# Bathroom_Board.net
KiCad netlist of a schematic drawn in EAGLE
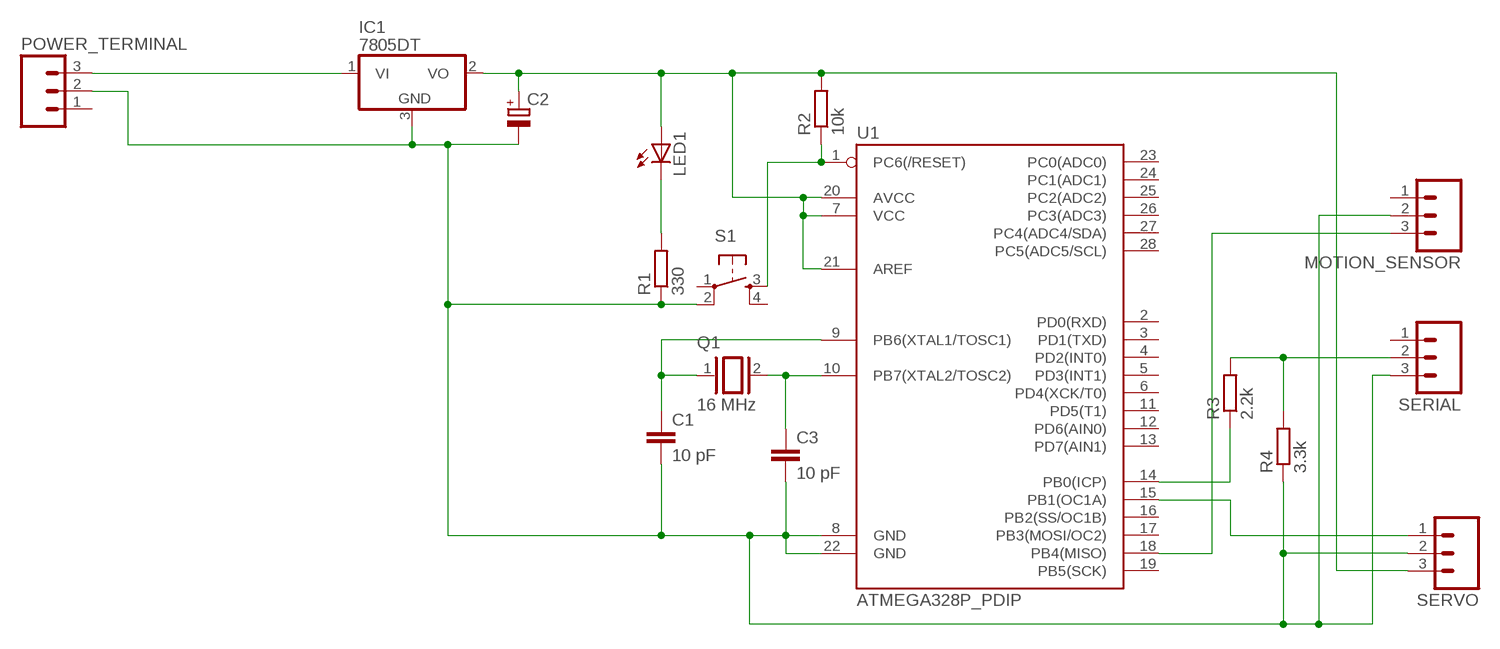
[diagram p0: schematic, sheet 1]

(export (version "E")
  (design (tool "Eeschema 10.0.6"))
  (components
    (comp (ref "C1")
      (value "10 pF")
      (footprint "eagle-import:C025-050X050")
      (libsource (lib "eagle-import") (part "C-EU025-050X050"))
    )
    (comp (ref "C2")
      (value "CPOL-EU153CLV-0505")
      (footprint "eagle-import:153CLV-0505")
      (libsource (lib "eagle-import") (part "CPOL-EU153CLV-0505"))
    )
    (comp (ref "C3")
      (value "10 pF")
      (footprint "eagle-import:C025-050X050")
      (libsource (lib "eagle-import") (part "C-EU025-050X050"))
    )
    (comp (ref "IC1")
      (value "7805DT")
      (footprint "eagle-import:TO252")
      (libsource (lib "eagle-import") (part "78DT05"))
    )
    (comp (ref "LED1")
      (value "LED5MM")
      (footprint "eagle-import:LED5MM")
      (libsource (lib "eagle-import") (part "LED5MM"))
    )
    (comp (ref "MOTION_SENSOR")
      (value "M03-SCREW-5MM")
      (footprint "eagle-import:SCREWTERMINAL-5MM-3")
      (libsource (lib "eagle-import") (part "M03-SCREW-5MM"))
    )
    (comp (ref "POWER_TERMINAL")
      (value "M03-SCREW-5MM")
      (footprint "eagle-import:SCREWTERMINAL-5MM-3")
      (libsource (lib "eagle-import") (part "M03-SCREW-5MM"))
    )
    (comp (ref "Q1")
      (value "16 MHz")
      (footprint "eagle-import:QS")
      (libsource (lib "eagle-import") (part "XTAL/S"))
    )
    (comp (ref "R1")
      (value "330")
      (footprint "eagle-import:0411_12")
      (libsource (lib "eagle-import") (part "R-EU_0411/12"))
    )
    (comp (ref "R2")
      (value "10k")
      (footprint "eagle-import:0411_12")
      (libsource (lib "eagle-import") (part "R-EU_0411/12"))
    )
    (comp (ref "R3")
      (value "2.2k")
      (footprint "eagle-import:0411_12")
      (libsource (lib "eagle-import") (part "R-EU_0411/12"))
    )
    (comp (ref "R4")
      (value "3.3k")
      (footprint "eagle-import:0411_12")
      (libsource (lib "eagle-import") (part "R-EU_0411/12"))
    )
    (comp (ref "S1")
      (value "TAC_SWITCHPTH")
      (footprint "eagle-import:TACTILE-PTH")
      (libsource (lib "eagle-import") (part "TAC_SWITCHPTH"))
    )
    (comp (ref "SERIAL")
      (value "M03LOCK")
      (footprint "eagle-import:1X03_LOCK")
      (libsource (lib "eagle-import") (part "M03LOCK"))
    )
    (comp (ref "SERVO")
      (value "M03LOCK")
      (footprint "eagle-import:1X03_LOCK")
      (libsource (lib "eagle-import") (part "M03LOCK"))
    )
    (comp (ref "U1")
      (value "ATMEGA328P_PDIP")
      (footprint "eagle-import:DIL28-3")
      (libsource (lib "eagle-import") (part "ATMEGA328P_PDIP"))
    )
  )
  (nets
    (net (code "1") (name "Net-(IC1-GND)") (class "Default")
      (node (ref "C1") (pin "2") (pinfunction "2_2") (pintype "passive"))
      (node (ref "C2") (pin "-") (pinfunction "-_-") (pintype "passive"))
      (node (ref "C3") (pin "2") (pinfunction "2_2") (pintype "passive"))
      (node (ref "IC1") (pin "3") (pinfunction "GND_3") (pintype "passive"))
      (node (ref "MOTION_SENSOR") (pin "2") (pinfunction "2_2") (pintype "passive"))
      (node (ref "POWER_TERMINAL") (pin "2") (pinfunction "2_2") (pintype "passive"))
      (node (ref "R1") (pin "1") (pinfunction "1_1") (pintype "passive"))
      (node (ref "R4") (pin "1") (pinfunction "1_1") (pintype "passive"))
      (node (ref "S1") (pin "2") (pinfunction "2_2") (pintype "passive"))
      (node (ref "SERIAL") (pin "3") (pinfunction "3_3") (pintype "passive"))
      (node (ref "SERVO") (pin "2") (pinfunction "2_2") (pintype "passive"))
      (node (ref "U1") (pin "22") (pinfunction "GND_22") (pintype "bidirectional"))
      (node (ref "U1") (pin "8") (pinfunction "GND_8") (pintype "bidirectional"))
    )
    (net (code "2") (name "Net-(IC1-VI)") (class "Default")
      (node (ref "IC1") (pin "1") (pinfunction "VI_1") (pintype "input"))
      (node (ref "POWER_TERMINAL") (pin "3") (pinfunction "3_3") (pintype "passive"))
    )
    (net (code "3") (name "Net-(IC1-VO)") (class "Default")
      (node (ref "C2") (pin "+") (pinfunction "+_+") (pintype "passive"))
      (node (ref "IC1") (pin "2") (pinfunction "VO_2") (pintype "passive"))
      (node (ref "LED1") (pin "A") (pinfunction "A_A") (pintype "passive"))
      (node (ref "R2") (pin "2") (pinfunction "2_2") (pintype "passive"))
      (node (ref "SERVO") (pin "3") (pinfunction "3_3") (pintype "passive"))
      (node (ref "U1") (pin "20") (pinfunction "AVCC_20") (pintype "bidirectional"))
      (node (ref "U1") (pin "21") (pinfunction "AREF_21") (pintype "bidirectional"))
      (node (ref "U1") (pin "7") (pinfunction "VCC_7") (pintype "bidirectional"))
    )
    (net (code "4") (name "Net-(LED1-C)") (class "Default")
      (node (ref "LED1") (pin "K") (pinfunction "C_K") (pintype "passive"))
      (node (ref "R1") (pin "2") (pinfunction "2_2") (pintype "passive"))
    )
    (net (code "5") (name "Net-(R3-Pad2)") (class "Default")
      (node (ref "R3") (pin "2") (pinfunction "2_2") (pintype "passive"))
      (node (ref "R4") (pin "2") (pinfunction "2_2") (pintype "passive"))
      (node (ref "SERIAL") (pin "2") (pinfunction "2_2") (pintype "passive"))
    )
    (net (code "6") (name "Net-(U1-PB0(ICP))") (class "Default")
      (node (ref "R3") (pin "1") (pinfunction "1_1") (pintype "passive"))
      (node (ref "U1") (pin "14") (pinfunction "PB0(ICP)_14") (pintype "bidirectional"))
    )
    (net (code "7") (name "Net-(U1-PB1(OC1A))") (class "Default")
      (node (ref "SERVO") (pin "1") (pinfunction "1_1") (pintype "passive"))
      (node (ref "U1") (pin "15") (pinfunction "PB1(OC1A)_15") (pintype "bidirectional"))
    )
    (net (code "8") (name "Net-(U1-PB4(MISO))") (class "Default")
      (node (ref "MOTION_SENSOR") (pin "3") (pinfunction "3_3") (pintype "passive"))
      (node (ref "U1") (pin "18") (pinfunction "PB4(MISO)_18") (pintype "bidirectional"))
    )
    (net (code "9") (name "Net-(U1-PB6(XTAL1{slash}TOSC1))") (class "Default")
      (node (ref "C1") (pin "1") (pinfunction "1_1") (pintype "passive"))
      (node (ref "Q1") (pin "1") (pinfunction "1_1") (pintype "passive"))
      (node (ref "U1") (pin "9") (pinfunction "PB6(XTAL1/TOSC1)_9") (pintype "bidirectional"))
    )
    (net (code "10") (name "Net-(U1-PB7(XTAL2{slash}TOSC2))") (class "Default")
      (node (ref "C3") (pin "1") (pinfunction "1_1") (pintype "passive"))
      (node (ref "Q1") (pin "2") (pinfunction "2_2") (pintype "passive"))
      (node (ref "U1") (pin "10") (pinfunction "PB7(XTAL2/TOSC2)_10") (pintype "bidirectional"))
    )
    (net (code "11") (name "Net-(U1-PC6({slash}RESET))") (class "Default")
      (node (ref "R2") (pin "1") (pinfunction "1_1") (pintype "passive"))
      (node (ref "S1") (pin "3") (pinfunction "3_3") (pintype "passive"))
      (node (ref "U1") (pin "1") (pinfunction "PC6(/RESET)_1") (pintype "bidirectional"))
    )
    (net (code "12") (name "unconnected-(MOTION_SENSOR-Pad1)") (class "Default")
      (node (ref "MOTION_SENSOR") (pin "1") (pinfunction "1_1") (pintype "passive"))
    )
    (net (code "13") (name "unconnected-(POWER_TERMINAL-Pad1)") (class "Default")
      (node (ref "POWER_TERMINAL") (pin "1") (pinfunction "1_1") (pintype "passive"))
    )
    (net (code "14") (name "unconnected-(S1-Pad1)") (class "Default")
      (node (ref "S1") (pin "1") (pinfunction "1_1") (pintype "passive"))
    )
    (net (code "15") (name "unconnected-(S1-Pad4)") (class "Default")
      (node (ref "S1") (pin "4") (pinfunction "4_4") (pintype "passive"))
    )
    (net (code "16") (name "unconnected-(SERIAL-Pad1)") (class "Default")
      (node (ref "SERIAL") (pin "1") (pinfunction "1_1") (pintype "passive"))
    )
    (net (code "17") (name "unconnected-(U1-PB2(SS{slash}OC1B)-Pad16)") (class "Default")
      (node (ref "U1") (pin "16") (pinfunction "PB2(SS/OC1B)_16") (pintype "bidirectional"))
    )
    (net (code "18") (name "unconnected-(U1-PB3(MOSI{slash}OC2)-Pad17)") (class "Default")
      (node (ref "U1") (pin "17") (pinfunction "PB3(MOSI/OC2)_17") (pintype "bidirectional"))
    )
    (net (code "19") (name "unconnected-(U1-PB5(SCK)-Pad19)") (class "Default")
      (node (ref "U1") (pin "19") (pinfunction "PB5(SCK)_19") (pintype "bidirectional"))
    )
    (net (code "20") (name "unconnected-(U1-PC0(ADC0)-Pad23)") (class "Default")
      (node (ref "U1") (pin "23") (pinfunction "PC0(ADC0)_23") (pintype "bidirectional"))
    )
    (net (code "21") (name "unconnected-(U1-PC1(ADC1)-Pad24)") (class "Default")
      (node (ref "U1") (pin "24") (pinfunction "PC1(ADC1)_24") (pintype "bidirectional"))
    )
    (net (code "22") (name "unconnected-(U1-PC2(ADC2)-Pad25)") (class "Default")
      (node (ref "U1") (pin "25") (pinfunction "PC2(ADC2)_25") (pintype "bidirectional"))
    )
    (net (code "23") (name "unconnected-(U1-PC3(ADC3)-Pad26)") (class "Default")
      (node (ref "U1") (pin "26") (pinfunction "PC3(ADC3)_26") (pintype "bidirectional"))
    )
    (net (code "24") (name "unconnected-(U1-PC4(ADC4{slash}SDA)-Pad27)") (class "Default")
      (node (ref "U1") (pin "27") (pinfunction "PC4(ADC4/SDA)_27") (pintype "bidirectional"))
    )
    (net (code "25") (name "unconnected-(U1-PC5(ADC5{slash}SCL)-Pad28)") (class "Default")
      (node (ref "U1") (pin "28") (pinfunction "PC5(ADC5/SCL)_28") (pintype "bidirectional"))
    )
    (net (code "26") (name "unconnected-(U1-PD0(RXD)-Pad2)") (class "Default")
      (node (ref "U1") (pin "2") (pinfunction "PD0(RXD)_2") (pintype "bidirectional"))
    )
    (net (code "27") (name "unconnected-(U1-PD1(TXD)-Pad3)") (class "Default")
      (node (ref "U1") (pin "3") (pinfunction "PD1(TXD)_3") (pintype "bidirectional"))
    )
    (net (code "28") (name "unconnected-(U1-PD2(INT0)-Pad4)") (class "Default")
      (node (ref "U1") (pin "4") (pinfunction "PD2(INT0)_4") (pintype "bidirectional"))
    )
    (net (code "29") (name "unconnected-(U1-PD3(INT1)-Pad5)") (class "Default")
      (node (ref "U1") (pin "5") (pinfunction "PD3(INT1)_5") (pintype "bidirectional"))
    )
    (net (code "30") (name "unconnected-(U1-PD4(XCK{slash}T0)-Pad6)") (class "Default")
      (node (ref "U1") (pin "6") (pinfunction "PD4(XCK/T0)_6") (pintype "bidirectional"))
    )
    (net (code "31") (name "unconnected-(U1-PD5(T1)-Pad11)") (class "Default")
      (node (ref "U1") (pin "11") (pinfunction "PD5(T1)_11") (pintype "bidirectional"))
    )
    (net (code "32") (name "unconnected-(U1-PD6(AIN0)-Pad12)") (class "Default")
      (node (ref "U1") (pin "12") (pinfunction "PD6(AIN0)_12") (pintype "bidirectional"))
    )
    (net (code "33") (name "unconnected-(U1-PD7(AIN1)-Pad13)") (class "Default")
      (node (ref "U1") (pin "13") (pinfunction "PD7(AIN1)_13") (pintype "bidirectional"))
    )
  )
)
